# TCU.net
KiCad netlist of a schematic drawn in EAGLE
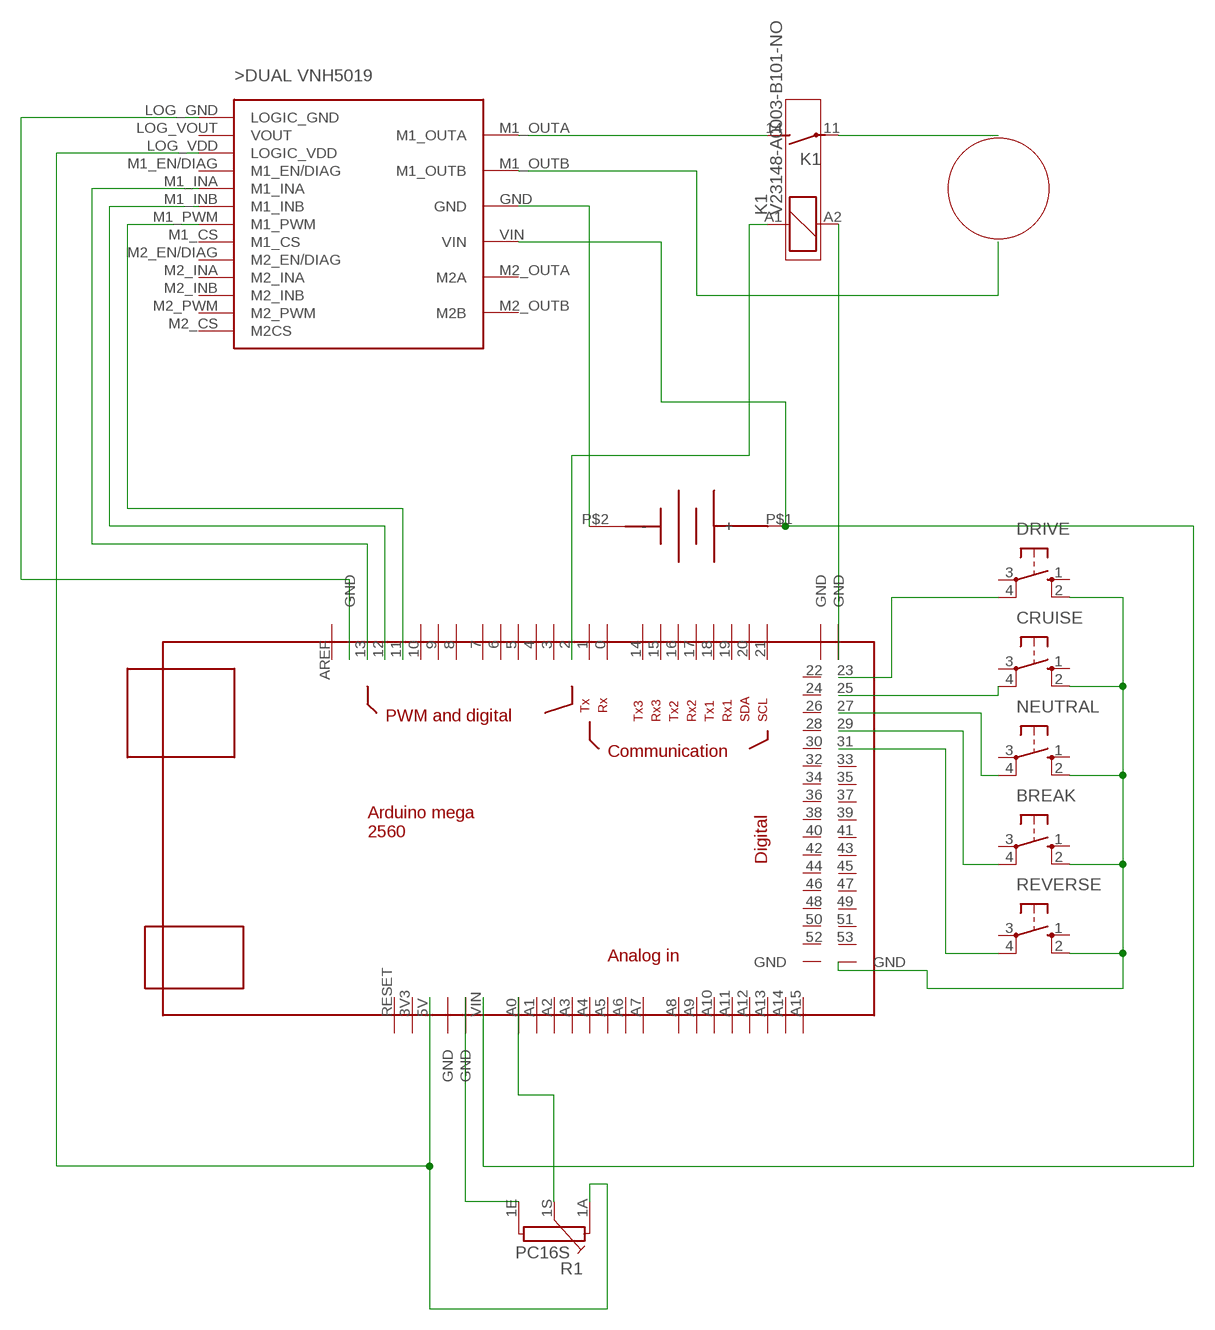
[diagram p0: schematic, sheet 1]

(export (version "E")
  (design (tool "Eeschema 10.0.6"))
  (components
    (comp (ref "BREAK")
      (value "10-XX")
      (footprint "eagle-import:B3F-10XX")
      (fields (field (name "MPN") "B3F-1000"))
      (libsource (lib "eagle-import") (part "10-XX"))
    )
    (comp (ref "CRUISE")
      (value "10-XX")
      (footprint "eagle-import:B3F-10XX")
      (fields (field (name "MPN") "B3F-1000"))
      (libsource (lib "eagle-import") (part "10-XX"))
    )
    (comp (ref "DRIVE")
      (value "10-XX")
      (footprint "eagle-import:B3F-10XX")
      (fields (field (name "MPN") "B3F-1000"))
      (libsource (lib "eagle-import") (part "10-XX"))
    )
    (comp (ref "DUAL_VNH1")
      (value "DUAL_VNH5019")
      (footprint "eagle-import:DUAL_VNH5019")
      (libsource (lib "eagle-import") (part "DUAL_VNH5019"))
    )
    (comp (ref "K1")
      (value "V23148-A0003-B101-NO")
      (footprint "eagle-import:V23148-NO")
      (fields (field (name "MPN") "V23148-A0007-A101"))
      (libsource (lib "eagle-import") (part "V23148--NOA0003-B101"))
    )
    (comp (ref "NEUTRAL")
      (value "10-XX")
      (footprint "eagle-import:B3F-10XX")
      (fields (field (name "MPN") "B3F-1000"))
      (libsource (lib "eagle-import") (part "10-XX"))
    )
    (comp (ref "R1")
      (value "PC16S")
      (footprint "eagle-import:PC16S")
      (libsource (lib "eagle-import") (part "PC16S"))
    )
    (comp (ref "REVERSE")
      (value "10-XX")
      (footprint "eagle-import:B3F-10XX")
      (fields (field (name "MPN") "B3F-1000"))
      (libsource (lib "eagle-import") (part "10-XX"))
    )
    (comp (ref "U$1")
      (value "MEGA_DEVICE")
      (footprint "eagle-import:MEGABOX")
      (libsource (lib "eagle-import") (part "MEGA_DEVICE"))
    )
    (comp (ref "U$3")
      (value "12V-BATTERY")
      (footprint "eagle-import:12V-BATTERY")
      (libsource (lib "eagle-import") (part "12V-BATTERY"))
    )
  )
  (nets
    (net (code "1") (name "Net-(BREAK-P1)") (class "Default")
      (node (ref "BREAK") (pin "4") (pinfunction "P1_4") (pintype "passive"))
      (node (ref "U$1") (pin "29") (pinfunction "29_29") (pintype "bidirectional"))
    )
    (net (code "2") (name "Net-(BREAK-S1)") (class "Default")
      (node (ref "BREAK") (pin "2") (pinfunction "S1_2") (pintype "passive"))
      (node (ref "CRUISE") (pin "2") (pinfunction "S1_2") (pintype "passive"))
      (node (ref "DRIVE") (pin "2") (pinfunction "S1_2") (pintype "passive"))
      (node (ref "NEUTRAL") (pin "2") (pinfunction "S1_2") (pintype "passive"))
      (node (ref "REVERSE") (pin "2") (pinfunction "S1_2") (pintype "passive"))
      (node (ref "U$1") (pin "GND@7") (pinfunction "GND_GND@7") (pintype "bidirectional"))
    )
    (net (code "3") (name "Net-(CRUISE-P1)") (class "Default")
      (node (ref "CRUISE") (pin "4") (pinfunction "P1_4") (pintype "passive"))
      (node (ref "U$1") (pin "25") (pinfunction "25_25") (pintype "bidirectional"))
    )
    (net (code "4") (name "Net-(DRIVE-P1)") (class "Default")
      (node (ref "DRIVE") (pin "4") (pinfunction "P1_4") (pintype "passive"))
      (node (ref "U$1") (pin "23") (pinfunction "23_23") (pintype "bidirectional"))
    )
    (net (code "5") (name "Net-(DUAL_VNH1-LOGIC_GND)") (class "Default")
      (node (ref "DUAL_VNH1") (pin "LOG_GND") (pinfunction "LOGIC_GND_LOG_GND") (pintype "bidirectional"))
      (node (ref "U$1") (pin "GND@1") (pinfunction "GND_GND@1") (pintype "bidirectional"))
    )
    (net (code "6") (name "Net-(DUAL_VNH1-LOGIC_VDD)") (class "Default")
      (node (ref "DUAL_VNH1") (pin "LOG_VDD") (pinfunction "LOGIC_VDD_LOG_VDD") (pintype "bidirectional"))
      (node (ref "R1") (pin "1A") (pinfunction "1A_1A") (pintype "passive"))
      (node (ref "U$1") (pin "5V") (pinfunction "5V_5V") (pintype "bidirectional"))
    )
    (net (code "7") (name "Net-(DUAL_VNH1-PadM1_INA)") (class "Default")
      (node (ref "DUAL_VNH1") (pin "M1_INA") (pinfunction "M1_INA_M1_INA") (pintype "bidirectional"))
      (node (ref "U$1") (pin "13") (pinfunction "13_13") (pintype "bidirectional"))
    )
    (net (code "8") (name "Net-(DUAL_VNH1-PadM1_INB)") (class "Default")
      (node (ref "DUAL_VNH1") (pin "M1_INB") (pinfunction "M1_INB_M1_INB") (pintype "bidirectional"))
      (node (ref "U$1") (pin "12") (pinfunction "12_12") (pintype "bidirectional"))
    )
    (net (code "9") (name "Net-(DUAL_VNH1-PadM1_PWM)") (class "Default")
      (node (ref "DUAL_VNH1") (pin "M1_PWM") (pinfunction "M1_PWM_M1_PWM") (pintype "bidirectional"))
      (node (ref "U$1") (pin "11") (pinfunction "11_11") (pintype "bidirectional"))
    )
    (net (code "10") (name "Net-(K1A-1)") (class "Default")
      (node (ref "K1") (pin "A1") (pinfunction "1_A1") (pintype "passive"))
      (node (ref "U$1") (pin "2") (pinfunction "2_2") (pintype "bidirectional"))
    )
    (net (code "11") (name "Net-(K1A-2)") (class "Default")
      (node (ref "K1") (pin "A2") (pinfunction "2_A2") (pintype "passive"))
      (node (ref "U$1") (pin "GND@5") (pinfunction "GND_GND@5") (pintype "bidirectional"))
    )
    (net (code "12") (name "Net-(K1B-S)") (class "Default")
      (node (ref "DUAL_VNH1") (pin "M1_OUTA") (pinfunction "M1_OUTA_M1_OUTA") (pintype "bidirectional"))
      (node (ref "K1") (pin "14") (pinfunction "S_14") (pintype "passive"))
    )
    (net (code "13") (name "Net-(NEUTRAL-P1)") (class "Default")
      (node (ref "NEUTRAL") (pin "4") (pinfunction "P1_4") (pintype "passive"))
      (node (ref "U$1") (pin "27") (pinfunction "27_27") (pintype "bidirectional"))
    )
    (net (code "14") (name "Net-(R1-Pad1E)") (class "Default")
      (node (ref "R1") (pin "1E") (pinfunction "1E_1E") (pintype "passive"))
      (node (ref "U$1") (pin "GND@3") (pinfunction "GND_GND@3") (pintype "bidirectional"))
    )
    (net (code "15") (name "Net-(R1-Pad1S)") (class "Default")
      (node (ref "R1") (pin "1S") (pinfunction "1S_1S") (pintype "passive"))
      (node (ref "U$1") (pin "A0") (pinfunction "A0_A0") (pintype "bidirectional"))
    )
    (net (code "16") (name "Net-(REVERSE-P1)") (class "Default")
      (node (ref "REVERSE") (pin "4") (pinfunction "P1_4") (pintype "passive"))
      (node (ref "U$1") (pin "31") (pinfunction "31_31") (pintype "bidirectional"))
    )
    (net (code "17") (name "Net-(U$3-+)") (class "Default")
      (node (ref "DUAL_VNH1") (pin "VIN") (pinfunction "VIN_VIN") (pintype "bidirectional"))
      (node (ref "U$1") (pin "VIN") (pinfunction "VIN_VIN") (pintype "bidirectional"))
      (node (ref "U$3") (pin "P$1") (pinfunction "+_P$1") (pintype "bidirectional"))
    )
    (net (code "18") (name "Net-(U$3--)") (class "Default")
      (node (ref "DUAL_VNH1") (pin "GND") (pinfunction "GND_GND") (pintype "bidirectional"))
      (node (ref "U$3") (pin "P$2") (pinfunction "-_P$2") (pintype "bidirectional"))
    )
    (net (code "19") (name "unconnected-(BREAK-P-Pad3)") (class "Default")
      (node (ref "BREAK") (pin "3") (pinfunction "P_3") (pintype "passive"))
    )
    (net (code "20") (name "unconnected-(BREAK-S-Pad1)") (class "Default")
      (node (ref "BREAK") (pin "1") (pinfunction "S_1") (pintype "passive"))
    )
    (net (code "21") (name "unconnected-(CRUISE-P-Pad3)") (class "Default")
      (node (ref "CRUISE") (pin "3") (pinfunction "P_3") (pintype "passive"))
    )
    (net (code "22") (name "unconnected-(CRUISE-S-Pad1)") (class "Default")
      (node (ref "CRUISE") (pin "1") (pinfunction "S_1") (pintype "passive"))
    )
    (net (code "23") (name "unconnected-(DRIVE-P-Pad3)") (class "Default")
      (node (ref "DRIVE") (pin "3") (pinfunction "P_3") (pintype "passive"))
    )
    (net (code "24") (name "unconnected-(DRIVE-S-Pad1)") (class "Default")
      (node (ref "DRIVE") (pin "1") (pinfunction "S_1") (pintype "passive"))
    )
    (net (code "25") (name "unconnected-(DUAL_VNH1-M2A-PadM2_OUTA)") (class "Default")
      (node (ref "DUAL_VNH1") (pin "M2_OUTA") (pinfunction "M2A_M2_OUTA") (pintype "bidirectional"))
    )
    (net (code "26") (name "unconnected-(DUAL_VNH1-M2B-PadM2_OUTB)") (class "Default")
      (node (ref "DUAL_VNH1") (pin "M2_OUTB") (pinfunction "M2B_M2_OUTB") (pintype "bidirectional"))
    )
    (net (code "27") (name "unconnected-(DUAL_VNH1-M2CS-PadM2_CS)") (class "Default")
      (node (ref "DUAL_VNH1") (pin "M2_CS") (pinfunction "M2CS_M2_CS") (pintype "bidirectional"))
    )
    (net (code "28") (name "unconnected-(DUAL_VNH1-PadM1_CS)") (class "Default")
      (node (ref "DUAL_VNH1") (pin "M1_CS") (pinfunction "M1_CS_M1_CS") (pintype "bidirectional"))
    )
    (net (code "29") (name "unconnected-(DUAL_VNH1-PadM1_EN{slash}DIAG)") (class "Default")
      (node (ref "DUAL_VNH1") (pin "M1_EN/DIAG") (pinfunction "M1_EN/DIAG_M1_EN/DIAG") (pintype "bidirectional"))
    )
    (net (code "30") (name "unconnected-(DUAL_VNH1-PadM1_OUTB)") (class "Default")
      (node (ref "DUAL_VNH1") (pin "M1_OUTB") (pinfunction "M1_OUTB_M1_OUTB") (pintype "bidirectional"))
    )
    (net (code "31") (name "unconnected-(DUAL_VNH1-PadM2_EN{slash}DIAG)") (class "Default")
      (node (ref "DUAL_VNH1") (pin "M2_EN/DIAG") (pinfunction "M2_EN/DIAG_M2_EN/DIAG") (pintype "bidirectional"))
    )
    (net (code "32") (name "unconnected-(DUAL_VNH1-PadM2_INA)") (class "Default")
      (node (ref "DUAL_VNH1") (pin "M2_INA") (pinfunction "M2_INA_M2_INA") (pintype "bidirectional"))
    )
    (net (code "33") (name "unconnected-(DUAL_VNH1-PadM2_INB)") (class "Default")
      (node (ref "DUAL_VNH1") (pin "M2_INB") (pinfunction "M2_INB_M2_INB") (pintype "bidirectional"))
    )
    (net (code "34") (name "unconnected-(DUAL_VNH1-PadM2_PWM)") (class "Default")
      (node (ref "DUAL_VNH1") (pin "M2_PWM") (pinfunction "M2_PWM_M2_PWM") (pintype "bidirectional"))
    )
    (net (code "35") (name "unconnected-(DUAL_VNH1-VOUT-PadLOG_VOUT)") (class "Default")
      (node (ref "DUAL_VNH1") (pin "LOG_VOUT") (pinfunction "VOUT_LOG_VOUT") (pintype "bidirectional"))
    )
    (net (code "36") (name "unconnected-(K1B-P-Pad11)") (class "Default")
      (node (ref "K1") (pin "11") (pinfunction "P_11") (pintype "passive"))
    )
    (net (code "37") (name "unconnected-(NEUTRAL-P-Pad3)") (class "Default")
      (node (ref "NEUTRAL") (pin "3") (pinfunction "P_3") (pintype "passive"))
    )
    (net (code "38") (name "unconnected-(NEUTRAL-S-Pad1)") (class "Default")
      (node (ref "NEUTRAL") (pin "1") (pinfunction "S_1") (pintype "passive"))
    )
    (net (code "39") (name "unconnected-(REVERSE-P-Pad3)") (class "Default")
      (node (ref "REVERSE") (pin "3") (pinfunction "P_3") (pintype "passive"))
    )
    (net (code "40") (name "unconnected-(REVERSE-S-Pad1)") (class "Default")
      (node (ref "REVERSE") (pin "1") (pinfunction "S_1") (pintype "passive"))
    )
    (net (code "41") (name "unconnected-(U$1-GND-PadGND@2)") (class "Default")
      (node (ref "U$1") (pin "GND@2") (pinfunction "GND_GND@2") (pintype "bidirectional"))
    )
    (net (code "42") (name "unconnected-(U$1-GND-PadGND@4)") (class "Default")
      (node (ref "U$1") (pin "GND@4") (pinfunction "GND_GND@4") (pintype "bidirectional"))
    )
    (net (code "43") (name "unconnected-(U$1-GND-PadGND@6)") (class "Default")
      (node (ref "U$1") (pin "GND@6") (pinfunction "GND_GND@6") (pintype "bidirectional"))
    )
    (net (code "44") (name "unconnected-(U$1-Pad0)") (class "Default")
      (node (ref "U$1") (pin "0") (pinfunction "0_0") (pintype "bidirectional"))
    )
    (net (code "45") (name "unconnected-(U$1-Pad1)") (class "Default")
      (node (ref "U$1") (pin "1") (pinfunction "1_1") (pintype "bidirectional"))
    )
    (net (code "46") (name "unconnected-(U$1-Pad3)") (class "Default")
      (node (ref "U$1") (pin "3") (pinfunction "3_3") (pintype "bidirectional"))
    )
    (net (code "47") (name "unconnected-(U$1-Pad3V3)") (class "Default")
      (node (ref "U$1") (pin "3V3") (pinfunction "3V3_3V3") (pintype "bidirectional"))
    )
    (net (code "48") (name "unconnected-(U$1-Pad4)") (class "Default")
      (node (ref "U$1") (pin "4") (pinfunction "4_4") (pintype "bidirectional"))
    )
    (net (code "49") (name "unconnected-(U$1-Pad5)") (class "Default")
      (node (ref "U$1") (pin "5") (pinfunction "5_5") (pintype "bidirectional"))
    )
    (net (code "50") (name "unconnected-(U$1-Pad6)") (class "Default")
      (node (ref "U$1") (pin "6") (pinfunction "6_6") (pintype "bidirectional"))
    )
    (net (code "51") (name "unconnected-(U$1-Pad7)") (class "Default")
      (node (ref "U$1") (pin "7") (pinfunction "7_7") (pintype "bidirectional"))
    )
    (net (code "52") (name "unconnected-(U$1-Pad8)") (class "Default")
      (node (ref "U$1") (pin "8") (pinfunction "8_8") (pintype "bidirectional"))
    )
    (net (code "53") (name "unconnected-(U$1-Pad9)") (class "Default")
      (node (ref "U$1") (pin "9") (pinfunction "9_9") (pintype "bidirectional"))
    )
    (net (code "54") (name "unconnected-(U$1-Pad10)") (class "Default")
      (node (ref "U$1") (pin "10") (pinfunction "10_10") (pintype "bidirectional"))
    )
    (net (code "55") (name "unconnected-(U$1-Pad14)") (class "Default")
      (node (ref "U$1") (pin "14") (pinfunction "14_14") (pintype "bidirectional"))
    )
    (net (code "56") (name "unconnected-(U$1-Pad15)") (class "Default")
      (node (ref "U$1") (pin "15") (pinfunction "15_15") (pintype "bidirectional"))
    )
    (net (code "57") (name "unconnected-(U$1-Pad16)") (class "Default")
      (node (ref "U$1") (pin "16") (pinfunction "16_16") (pintype "bidirectional"))
    )
    (net (code "58") (name "unconnected-(U$1-Pad17)") (class "Default")
      (node (ref "U$1") (pin "17") (pinfunction "17_17") (pintype "bidirectional"))
    )
    (net (code "59") (name "unconnected-(U$1-Pad18)") (class "Default")
      (node (ref "U$1") (pin "18") (pinfunction "18_18") (pintype "bidirectional"))
    )
    (net (code "60") (name "unconnected-(U$1-Pad19)") (class "Default")
      (node (ref "U$1") (pin "19") (pinfunction "19_19") (pintype "bidirectional"))
    )
    (net (code "61") (name "unconnected-(U$1-Pad20)") (class "Default")
      (node (ref "U$1") (pin "20") (pinfunction "20_20") (pintype "bidirectional"))
    )
    (net (code "62") (name "unconnected-(U$1-Pad21)") (class "Default")
      (node (ref "U$1") (pin "21") (pinfunction "21_21") (pintype "bidirectional"))
    )
    (net (code "63") (name "unconnected-(U$1-Pad22)") (class "Default")
      (node (ref "U$1") (pin "22") (pinfunction "22_22") (pintype "bidirectional"))
    )
    (net (code "64") (name "unconnected-(U$1-Pad24)") (class "Default")
      (node (ref "U$1") (pin "24") (pinfunction "24_24") (pintype "bidirectional"))
    )
    (net (code "65") (name "unconnected-(U$1-Pad26)") (class "Default")
      (node (ref "U$1") (pin "26") (pinfunction "26_26") (pintype "bidirectional"))
    )
    (net (code "66") (name "unconnected-(U$1-Pad28)") (class "Default")
      (node (ref "U$1") (pin "28") (pinfunction "28_28") (pintype "bidirectional"))
    )
    (net (code "67") (name "unconnected-(U$1-Pad30)") (class "Default")
      (node (ref "U$1") (pin "30") (pinfunction "30_30") (pintype "bidirectional"))
    )
    (net (code "68") (name "unconnected-(U$1-Pad32)") (class "Default")
      (node (ref "U$1") (pin "32") (pinfunction "32_32") (pintype "bidirectional"))
    )
    (net (code "69") (name "unconnected-(U$1-Pad33)") (class "Default")
      (node (ref "U$1") (pin "33") (pinfunction "33_33") (pintype "bidirectional"))
    )
    (net (code "70") (name "unconnected-(U$1-Pad34)") (class "Default")
      (node (ref "U$1") (pin "34") (pinfunction "34_34") (pintype "bidirectional"))
    )
    (net (code "71") (name "unconnected-(U$1-Pad35)") (class "Default")
      (node (ref "U$1") (pin "35") (pinfunction "35_35") (pintype "bidirectional"))
    )
    (net (code "72") (name "unconnected-(U$1-Pad36)") (class "Default")
      (node (ref "U$1") (pin "36") (pinfunction "36_36") (pintype "bidirectional"))
    )
    (net (code "73") (name "unconnected-(U$1-Pad37)") (class "Default")
      (node (ref "U$1") (pin "37") (pinfunction "37_37") (pintype "bidirectional"))
    )
    (net (code "74") (name "unconnected-(U$1-Pad38)") (class "Default")
      (node (ref "U$1") (pin "38") (pinfunction "38_38") (pintype "bidirectional"))
    )
    (net (code "75") (name "unconnected-(U$1-Pad39)") (class "Default")
      (node (ref "U$1") (pin "39") (pinfunction "39_39") (pintype "bidirectional"))
    )
    (net (code "76") (name "unconnected-(U$1-Pad40)") (class "Default")
      (node (ref "U$1") (pin "40") (pinfunction "40_40") (pintype "bidirectional"))
    )
    (net (code "77") (name "unconnected-(U$1-Pad41)") (class "Default")
      (node (ref "U$1") (pin "41") (pinfunction "41_41") (pintype "bidirectional"))
    )
    (net (code "78") (name "unconnected-(U$1-Pad42)") (class "Default")
      (node (ref "U$1") (pin "42") (pinfunction "42_42") (pintype "bidirectional"))
    )
    (net (code "79") (name "unconnected-(U$1-Pad43)") (class "Default")
      (node (ref "U$1") (pin "43") (pinfunction "43_43") (pintype "bidirectional"))
    )
    (net (code "80") (name "unconnected-(U$1-Pad44)") (class "Default")
      (node (ref "U$1") (pin "44") (pinfunction "44_44") (pintype "bidirectional"))
    )
    (net (code "81") (name "unconnected-(U$1-Pad45)") (class "Default")
      (node (ref "U$1") (pin "45") (pinfunction "45_45") (pintype "bidirectional"))
    )
    (net (code "82") (name "unconnected-(U$1-Pad46)") (class "Default")
      (node (ref "U$1") (pin "46") (pinfunction "46_46") (pintype "bidirectional"))
    )
    (net (code "83") (name "unconnected-(U$1-Pad47)") (class "Default")
      (node (ref "U$1") (pin "47") (pinfunction "47_47") (pintype "bidirectional"))
    )
    (net (code "84") (name "unconnected-(U$1-Pad48)") (class "Default")
      (node (ref "U$1") (pin "48") (pinfunction "48_48") (pintype "bidirectional"))
    )
    (net (code "85") (name "unconnected-(U$1-Pad49)") (class "Default")
      (node (ref "U$1") (pin "49") (pinfunction "49_49") (pintype "bidirectional"))
    )
    (net (code "86") (name "unconnected-(U$1-Pad50)") (class "Default")
      (node (ref "U$1") (pin "50") (pinfunction "50_50") (pintype "bidirectional"))
    )
    (net (code "87") (name "unconnected-(U$1-Pad51)") (class "Default")
      (node (ref "U$1") (pin "51") (pinfunction "51_51") (pintype "bidirectional"))
    )
    (net (code "88") (name "unconnected-(U$1-Pad52)") (class "Default")
      (node (ref "U$1") (pin "52") (pinfunction "52_52") (pintype "bidirectional"))
    )
    (net (code "89") (name "unconnected-(U$1-Pad53)") (class "Default")
      (node (ref "U$1") (pin "53") (pinfunction "53_53") (pintype "bidirectional"))
    )
    (net (code "90") (name "unconnected-(U$1-PadA1)") (class "Default")
      (node (ref "U$1") (pin "A1") (pinfunction "A1_A1") (pintype "bidirectional"))
    )
    (net (code "91") (name "unconnected-(U$1-PadA2)") (class "Default")
      (node (ref "U$1") (pin "A2") (pinfunction "A2_A2") (pintype "bidirectional"))
    )
    (net (code "92") (name "unconnected-(U$1-PadA3)") (class "Default")
      (node (ref "U$1") (pin "A3") (pinfunction "A3_A3") (pintype "bidirectional"))
    )
    (net (code "93") (name "unconnected-(U$1-PadA4)") (class "Default")
      (node (ref "U$1") (pin "A4") (pinfunction "A4_A4") (pintype "bidirectional"))
    )
    (net (code "94") (name "unconnected-(U$1-PadA5)") (class "Default")
      (node (ref "U$1") (pin "A5") (pinfunction "A5_A5") (pintype "bidirectional"))
    )
    (net (code "95") (name "unconnected-(U$1-PadA6)") (class "Default")
      (node (ref "U$1") (pin "A6") (pinfunction "A6_A6") (pintype "bidirectional"))
    )
    (net (code "96") (name "unconnected-(U$1-PadA7)") (class "Default")
      (node (ref "U$1") (pin "A7") (pinfunction "A7_A7") (pintype "bidirectional"))
    )
    (net (code "97") (name "unconnected-(U$1-PadA8)") (class "Default")
      (node (ref "U$1") (pin "A8") (pinfunction "A8_A8") (pintype "bidirectional"))
    )
    (net (code "98") (name "unconnected-(U$1-PadA9)") (class "Default")
      (node (ref "U$1") (pin "A9") (pinfunction "A9_A9") (pintype "bidirectional"))
    )
    (net (code "99") (name "unconnected-(U$1-PadA10)") (class "Default")
      (node (ref "U$1") (pin "A10") (pinfunction "A10_A10") (pintype "bidirectional"))
    )
    (net (code "100") (name "unconnected-(U$1-PadA11)") (class "Default")
      (node (ref "U$1") (pin "A11") (pinfunction "A11_A11") (pintype "bidirectional"))
    )
    (net (code "101") (name "unconnected-(U$1-PadA12)") (class "Default")
      (node (ref "U$1") (pin "A12") (pinfunction "A12_A12") (pintype "bidirectional"))
    )
    (net (code "102") (name "unconnected-(U$1-PadA13)") (class "Default")
      (node (ref "U$1") (pin "A13") (pinfunction "A13_A13") (pintype "bidirectional"))
    )
    (net (code "103") (name "unconnected-(U$1-PadA14)") (class "Default")
      (node (ref "U$1") (pin "A14") (pinfunction "A14_A14") (pintype "bidirectional"))
    )
    (net (code "104") (name "unconnected-(U$1-PadA15)") (class "Default")
      (node (ref "U$1") (pin "A15") (pinfunction "A15_A15") (pintype "bidirectional"))
    )
    (net (code "105") (name "unconnected-(U$1-PadAREF)") (class "Default")
      (node (ref "U$1") (pin "AREF") (pinfunction "AREF_AREF") (pintype "bidirectional"))
    )
    (net (code "106") (name "unconnected-(U$1-PadRESET)") (class "Default")
      (node (ref "U$1") (pin "RESET") (pinfunction "RESET_RESET") (pintype "bidirectional"))
    )
  )
)
